# Sheet1.net
KiCad netlist of a schematic drawn in Altium Designer
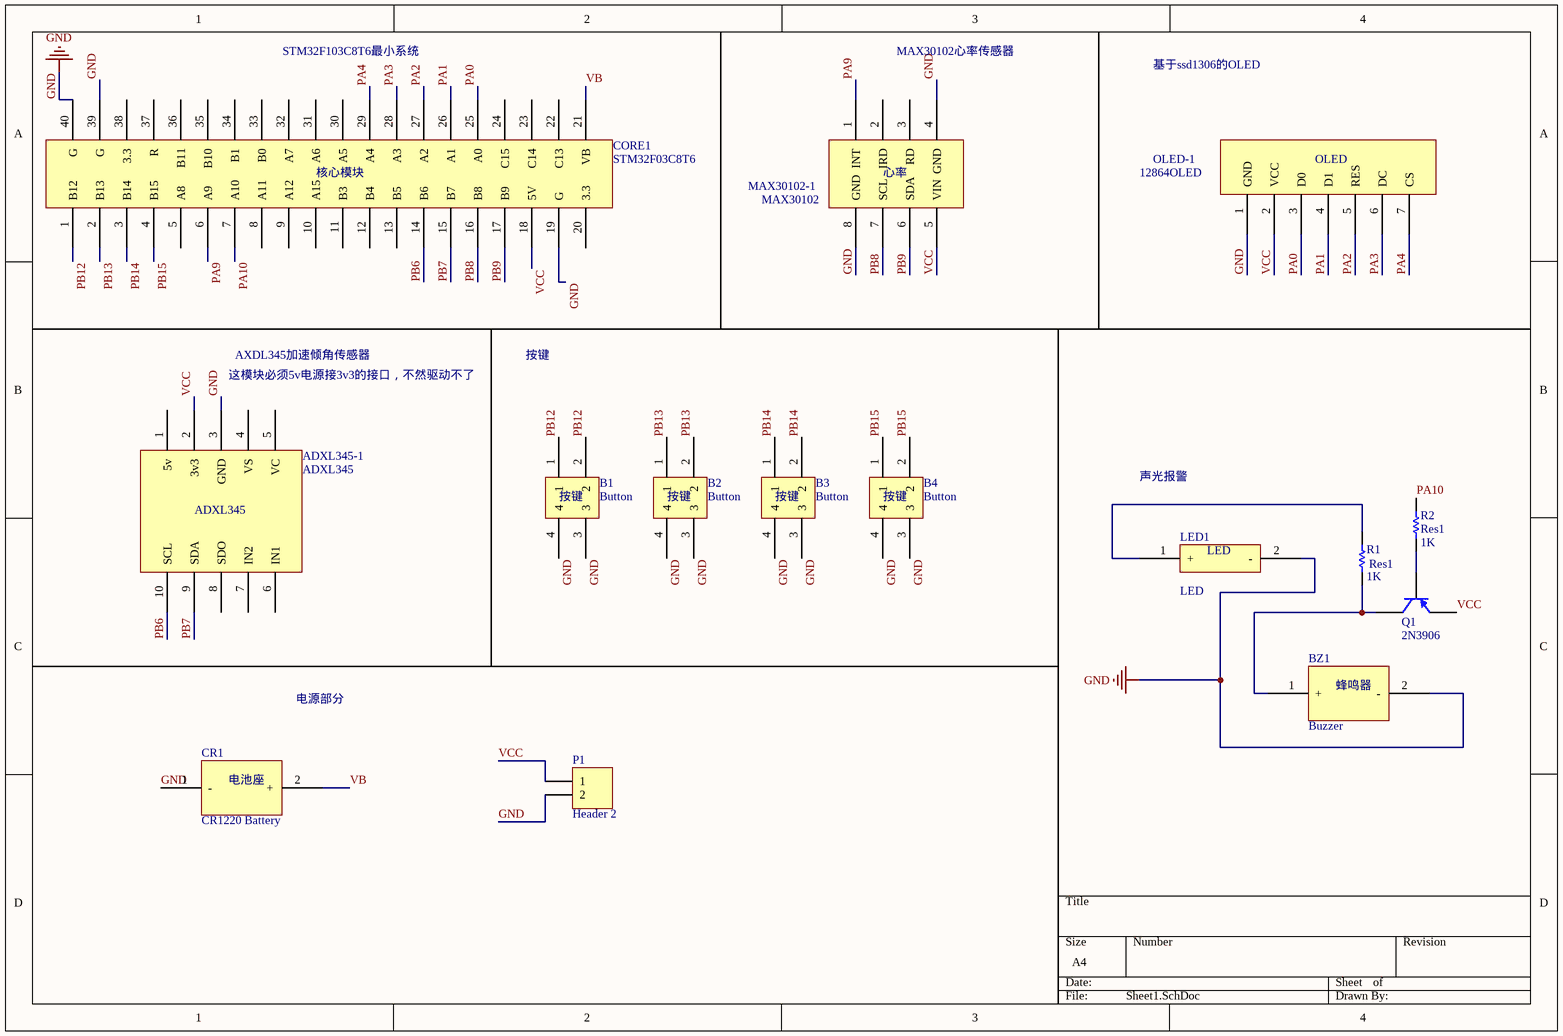
[diagram p0: Sheet1.SchDoc]

(export (version "E")
  (design (tool "Eeschema 10.0.6"))
  (components
    (comp (ref "ADXL345-1")
      (value "ADXL345")
      (footprint "ADXL345")
      (libsource (lib "Schlib1") (part "ADXL345"))
    )
    (comp (ref "B1") (value "Button") (footprint "Button") (libsource (lib "Schlib1") (part "Button")))
    (comp (ref "B2") (value "Button") (footprint "Button") (libsource (lib "Schlib1") (part "Button")))
    (comp (ref "B3") (value "Button") (footprint "Button") (libsource (lib "Schlib1") (part "Button")))
    (comp (ref "B4") (value "Button") (footprint "Button") (libsource (lib "Schlib1") (part "Button")))
    (comp (ref "BZ1") (value "Buzzer") (footprint "Buzzer") (libsource (lib "Schlib1") (part "Buzzer")))
    (comp (ref "CORE1")
      (value "STM32F03C8T6")
      (footprint "STM32F103C8T6")
      (libsource (lib "Schlib1") (part "STM32F03C8T6"))
    )
    (comp (ref "CR1")
      (value "CR1220 Battery")
      (footprint "CR1220 Battery")
      (libsource (lib "Schlib1") (part "CR1220 Battery"))
    )
    (comp (ref "LED1") (value "LED") (footprint "LED") (libsource (lib "Schlib1") (part "LED")))
    (comp (ref "MAX30102-1")
      (value "MAX30102")
      (footprint "MAX30102")
      (libsource (lib "Schlib1") (part "MAX30102"))
    )
    (comp (ref "OLED-1")
      (value "12864OLED")
      (footprint "OLED")
      (libsource (lib "Schlib1") (part "12864OLED"))
    )
    (comp (ref "P1")
      (value "Header 2")
      (footprint "HDR1X2")
      (description "Header, 2-Pin")
      (fields (field (name "PUBLISHER") "Altium Limited"))
      (libsource (lib "Miscellaneous Connectors") (part "Header 2"))
    )
    (comp (ref "Q1")
      (value "2N3906")
      (footprint "TO-92A")
      (description "PNP General Purpose Amplifier")
      (fields (field (name "PUBLISHER") "Altium Limited"))
      (libsource (lib "Miscellaneous Devices") (part "2N3906"))
    )
    (comp (ref "R1")
      (value "Res1")
      (footprint "AXIAL-0.3")
      (description "Resistor")
      (fields (field (name "ALTIUM_VALUE") "1K") (field (name "PUBLISHER") "Altium Limited"))
      (libsource (lib "Miscellaneous Devices") (part "Res1"))
    )
    (comp (ref "R2")
      (value "Res1")
      (footprint "AXIAL-0.3")
      (description "Resistor")
      (fields (field (name "ALTIUM_VALUE") "1K") (field (name "PUBLISHER") "Altium Limited"))
      (libsource (lib "Miscellaneous Devices") (part "Res1"))
    )
  )
  (nets
    (net (code "1") (name "/PA0") (class "Default")
      (node (ref "CORE1") (pin "25") (pinfunction "A0_25") (pintype "passive"))
      (node (ref "OLED-1") (pin "3") (pinfunction "D0_3") (pintype "passive"))
    )
    (net (code "2") (name "/PA1") (class "Default")
      (node (ref "CORE1") (pin "26") (pinfunction "A1_26") (pintype "passive"))
      (node (ref "OLED-1") (pin "4") (pinfunction "D1_4") (pintype "passive"))
    )
    (net (code "3") (name "/PA2") (class "Default")
      (node (ref "CORE1") (pin "27") (pinfunction "A2_27") (pintype "passive"))
      (node (ref "OLED-1") (pin "5") (pinfunction "RES_5") (pintype "passive"))
    )
    (net (code "4") (name "/PA3") (class "Default")
      (node (ref "CORE1") (pin "28") (pinfunction "A3_28") (pintype "passive"))
      (node (ref "OLED-1") (pin "6") (pinfunction "DC_6") (pintype "passive"))
    )
    (net (code "5") (name "/PA4") (class "Default")
      (node (ref "CORE1") (pin "29") (pinfunction "A4_29") (pintype "passive"))
      (node (ref "OLED-1") (pin "7") (pinfunction "CS_7") (pintype "passive"))
    )
    (net (code "6") (name "/PA9") (class "Default")
      (node (ref "CORE1") (pin "6") (pinfunction "A9_6") (pintype "passive"))
      (node (ref "MAX30102-1") (pin "1") (pinfunction "INT_1") (pintype "passive"))
    )
    (net (code "7") (name "/PA10") (class "Default")
      (node (ref "CORE1") (pin "7") (pinfunction "A10_7") (pintype "passive"))
      (node (ref "R2") (pin "2") (pinfunction "2_2") (pintype "passive"))
    )
    (net (code "8") (name "/PB6") (class "Default")
      (node (ref "ADXL345-1") (pin "10") (pinfunction "SCL_10") (pintype "passive"))
      (node (ref "CORE1") (pin "14") (pinfunction "B6_14") (pintype "passive"))
    )
    (net (code "9") (name "/PB7") (class "Default")
      (node (ref "ADXL345-1") (pin "9") (pinfunction "SDA_9") (pintype "passive"))
      (node (ref "CORE1") (pin "15") (pinfunction "B7_15") (pintype "passive"))
    )
    (net (code "10") (name "/PB8") (class "Default")
      (node (ref "CORE1") (pin "16") (pinfunction "B8_16") (pintype "passive"))
      (node (ref "MAX30102-1") (pin "7") (pinfunction "SCL_7") (pintype "passive"))
    )
    (net (code "11") (name "/PB9") (class "Default")
      (node (ref "CORE1") (pin "17") (pinfunction "B9_17") (pintype "passive"))
      (node (ref "MAX30102-1") (pin "6") (pinfunction "SDA_6") (pintype "passive"))
    )
    (net (code "12") (name "/PB12") (class "Default")
      (node (ref "B1") (pin "1") (pinfunction "1_1") (pintype "passive"))
      (node (ref "B1") (pin "2") (pinfunction "2_2") (pintype "passive"))
      (node (ref "CORE1") (pin "1") (pinfunction "B12_1") (pintype "passive"))
    )
    (net (code "13") (name "/PB13") (class "Default")
      (node (ref "B2") (pin "1") (pinfunction "1_1") (pintype "passive"))
      (node (ref "B2") (pin "2") (pinfunction "2_2") (pintype "passive"))
      (node (ref "CORE1") (pin "2") (pinfunction "B13_2") (pintype "passive"))
    )
    (net (code "14") (name "/PB14") (class "Default")
      (node (ref "B3") (pin "1") (pinfunction "1_1") (pintype "passive"))
      (node (ref "B3") (pin "2") (pinfunction "2_2") (pintype "passive"))
      (node (ref "CORE1") (pin "3") (pinfunction "B14_3") (pintype "passive"))
    )
    (net (code "15") (name "/PB15") (class "Default")
      (node (ref "B4") (pin "1") (pinfunction "1_1") (pintype "passive"))
      (node (ref "B4") (pin "2") (pinfunction "2_2") (pintype "passive"))
      (node (ref "CORE1") (pin "4") (pinfunction "B15_4") (pintype "passive"))
    )
    (net (code "16") (name "/VB") (class "Default")
      (node (ref "CORE1") (pin "21") (pinfunction "VB_21") (pintype "passive"))
      (node (ref "CR1") (pin "2") (pinfunction "+_2") (pintype "passive"))
    )
    (net (code "17") (name "/VCC") (class "Default")
      (node (ref "ADXL345-1") (pin "2") (pinfunction "3v3_2") (pintype "passive"))
      (node (ref "CORE1") (pin "18") (pinfunction "5V_18") (pintype "passive"))
      (node (ref "MAX30102-1") (pin "5") (pinfunction "VIN_5") (pintype "passive"))
      (node (ref "OLED-1") (pin "2") (pinfunction "VCC_2") (pintype "passive"))
      (node (ref "P1") (pin "1") (pinfunction "1_1") (pintype "passive"))
      (node (ref "Q1") (pin "1") (pinfunction "E_1") (pintype "passive"))
    )
    (net (code "18") (name "GND") (class "Default")
      (node (ref "ADXL345-1") (pin "3") (pinfunction "GND_3") (pintype "passive"))
      (node (ref "B1") (pin "3") (pinfunction "3_3") (pintype "passive"))
      (node (ref "B1") (pin "4") (pinfunction "4_4") (pintype "passive"))
      (node (ref "B2") (pin "3") (pinfunction "3_3") (pintype "passive"))
      (node (ref "B2") (pin "4") (pinfunction "4_4") (pintype "passive"))
      (node (ref "B3") (pin "3") (pinfunction "3_3") (pintype "passive"))
      (node (ref "B3") (pin "4") (pinfunction "4_4") (pintype "passive"))
      (node (ref "B4") (pin "3") (pinfunction "3_3") (pintype "passive"))
      (node (ref "B4") (pin "4") (pinfunction "4_4") (pintype "passive"))
      (node (ref "BZ1") (pin "2") (pinfunction "-_2") (pintype "passive"))
      (node (ref "CORE1") (pin "19") (pinfunction "G_19") (pintype "passive"))
      (node (ref "CORE1") (pin "39") (pinfunction "G_39") (pintype "passive"))
      (node (ref "CORE1") (pin "40") (pinfunction "G_40") (pintype "passive"))
      (node (ref "CR1") (pin "1") (pinfunction "-_1") (pintype "passive"))
      (node (ref "LED1") (pin "2") (pinfunction "-_2") (pintype "passive"))
      (node (ref "MAX30102-1") (pin "4") (pinfunction "GND_4") (pintype "passive"))
      (node (ref "MAX30102-1") (pin "8") (pinfunction "GND_8") (pintype "passive"))
      (node (ref "OLED-1") (pin "1") (pinfunction "GND_1") (pintype "passive"))
      (node (ref "P1") (pin "2") (pinfunction "2_2") (pintype "passive"))
    )
    (net (code "19") (name "Net-(BZ1-+)") (class "Default")
      (node (ref "BZ1") (pin "1") (pinfunction "+_1") (pintype "passive"))
      (node (ref "Q1") (pin "3") (pinfunction "C_3") (pintype "passive"))
      (node (ref "R1") (pin "1") (pinfunction "1_1") (pintype "passive"))
    )
    (net (code "20") (name "Net-(LED1-+)") (class "Default")
      (node (ref "LED1") (pin "1") (pinfunction "+_1") (pintype "passive"))
      (node (ref "R1") (pin "2") (pinfunction "2_2") (pintype "passive"))
    )
    (net (code "21") (name "Net-(Q1-B)") (class "Default")
      (node (ref "Q1") (pin "2") (pinfunction "B_2") (pintype "passive"))
      (node (ref "R2") (pin "1") (pinfunction "1_1") (pintype "passive"))
    )
    (net (code "22") (name "unconnected-(ADXL345-1-5v-Pad1)") (class "Default")
      (node (ref "ADXL345-1") (pin "1") (pinfunction "5v_1") (pintype "passive"))
    )
    (net (code "23") (name "unconnected-(ADXL345-1-IN1-Pad6)") (class "Default")
      (node (ref "ADXL345-1") (pin "6") (pinfunction "IN1_6") (pintype "passive"))
    )
    (net (code "24") (name "unconnected-(ADXL345-1-IN2-Pad7)") (class "Default")
      (node (ref "ADXL345-1") (pin "7") (pinfunction "IN2_7") (pintype "passive"))
    )
    (net (code "25") (name "unconnected-(ADXL345-1-SDO-Pad8)") (class "Default")
      (node (ref "ADXL345-1") (pin "8") (pinfunction "SDO_8") (pintype "passive"))
    )
    (net (code "26") (name "unconnected-(ADXL345-1-VC-Pad5)") (class "Default")
      (node (ref "ADXL345-1") (pin "5") (pinfunction "VC_5") (pintype "passive"))
    )
    (net (code "27") (name "unconnected-(ADXL345-1-VS-Pad4)") (class "Default")
      (node (ref "ADXL345-1") (pin "4") (pinfunction "VS_4") (pintype "passive"))
    )
    (net (code "28") (name "unconnected-(CORE1-3.3-Pad20)") (class "Default")
      (node (ref "CORE1") (pin "20") (pinfunction "3.3_20") (pintype "passive"))
    )
    (net (code "29") (name "unconnected-(CORE1-3.3-Pad38)") (class "Default")
      (node (ref "CORE1") (pin "38") (pinfunction "3.3_38") (pintype "passive"))
    )
    (net (code "30") (name "unconnected-(CORE1-A5-Pad30)") (class "Default")
      (node (ref "CORE1") (pin "30") (pinfunction "A5_30") (pintype "passive"))
    )
    (net (code "31") (name "unconnected-(CORE1-A6-Pad31)") (class "Default")
      (node (ref "CORE1") (pin "31") (pinfunction "A6_31") (pintype "passive"))
    )
    (net (code "32") (name "unconnected-(CORE1-A7-Pad32)") (class "Default")
      (node (ref "CORE1") (pin "32") (pinfunction "A7_32") (pintype "passive"))
    )
    (net (code "33") (name "unconnected-(CORE1-A8-Pad5)") (class "Default")
      (node (ref "CORE1") (pin "5") (pinfunction "A8_5") (pintype "passive"))
    )
    (net (code "34") (name "unconnected-(CORE1-A11-Pad8)") (class "Default")
      (node (ref "CORE1") (pin "8") (pinfunction "A11_8") (pintype "passive"))
    )
    (net (code "35") (name "unconnected-(CORE1-A12-Pad9)") (class "Default")
      (node (ref "CORE1") (pin "9") (pinfunction "A12_9") (pintype "passive"))
    )
    (net (code "36") (name "unconnected-(CORE1-A15-Pad10)") (class "Default")
      (node (ref "CORE1") (pin "10") (pinfunction "A15_10") (pintype "passive"))
    )
    (net (code "37") (name "unconnected-(CORE1-B0-Pad33)") (class "Default")
      (node (ref "CORE1") (pin "33") (pinfunction "B0_33") (pintype "passive"))
    )
    (net (code "38") (name "unconnected-(CORE1-B1-Pad34)") (class "Default")
      (node (ref "CORE1") (pin "34") (pinfunction "B1_34") (pintype "passive"))
    )
    (net (code "39") (name "unconnected-(CORE1-B3-Pad11)") (class "Default")
      (node (ref "CORE1") (pin "11") (pinfunction "B3_11") (pintype "passive"))
    )
    (net (code "40") (name "unconnected-(CORE1-B4-Pad12)") (class "Default")
      (node (ref "CORE1") (pin "12") (pinfunction "B4_12") (pintype "passive"))
    )
    (net (code "41") (name "unconnected-(CORE1-B5-Pad13)") (class "Default")
      (node (ref "CORE1") (pin "13") (pinfunction "B5_13") (pintype "passive"))
    )
    (net (code "42") (name "unconnected-(CORE1-B10-Pad35)") (class "Default")
      (node (ref "CORE1") (pin "35") (pinfunction "B10_35") (pintype "passive"))
    )
    (net (code "43") (name "unconnected-(CORE1-B11-Pad36)") (class "Default")
      (node (ref "CORE1") (pin "36") (pinfunction "B11_36") (pintype "passive"))
    )
    (net (code "44") (name "unconnected-(CORE1-C13-Pad22)") (class "Default")
      (node (ref "CORE1") (pin "22") (pinfunction "C13_22") (pintype "passive"))
    )
    (net (code "45") (name "unconnected-(CORE1-C14-Pad23)") (class "Default")
      (node (ref "CORE1") (pin "23") (pinfunction "C14_23") (pintype "passive"))
    )
    (net (code "46") (name "unconnected-(CORE1-C15-Pad24)") (class "Default")
      (node (ref "CORE1") (pin "24") (pinfunction "C15_24") (pintype "passive"))
    )
    (net (code "47") (name "unconnected-(CORE1-R-Pad37)") (class "Default")
      (node (ref "CORE1") (pin "37") (pinfunction "R_37") (pintype "passive"))
    )
    (net (code "48") (name "unconnected-(MAX30102-1-IRD-Pad2)") (class "Default")
      (node (ref "MAX30102-1") (pin "2") (pinfunction "IRD_2") (pintype "passive"))
    )
    (net (code "49") (name "unconnected-(MAX30102-1-RD-Pad3)") (class "Default")
      (node (ref "MAX30102-1") (pin "3") (pinfunction "RD_3") (pintype "passive"))
    )
  )
)
